# ik_breakout__atxmega32E5.net
KiCad netlist of a schematic drawn in EAGLE
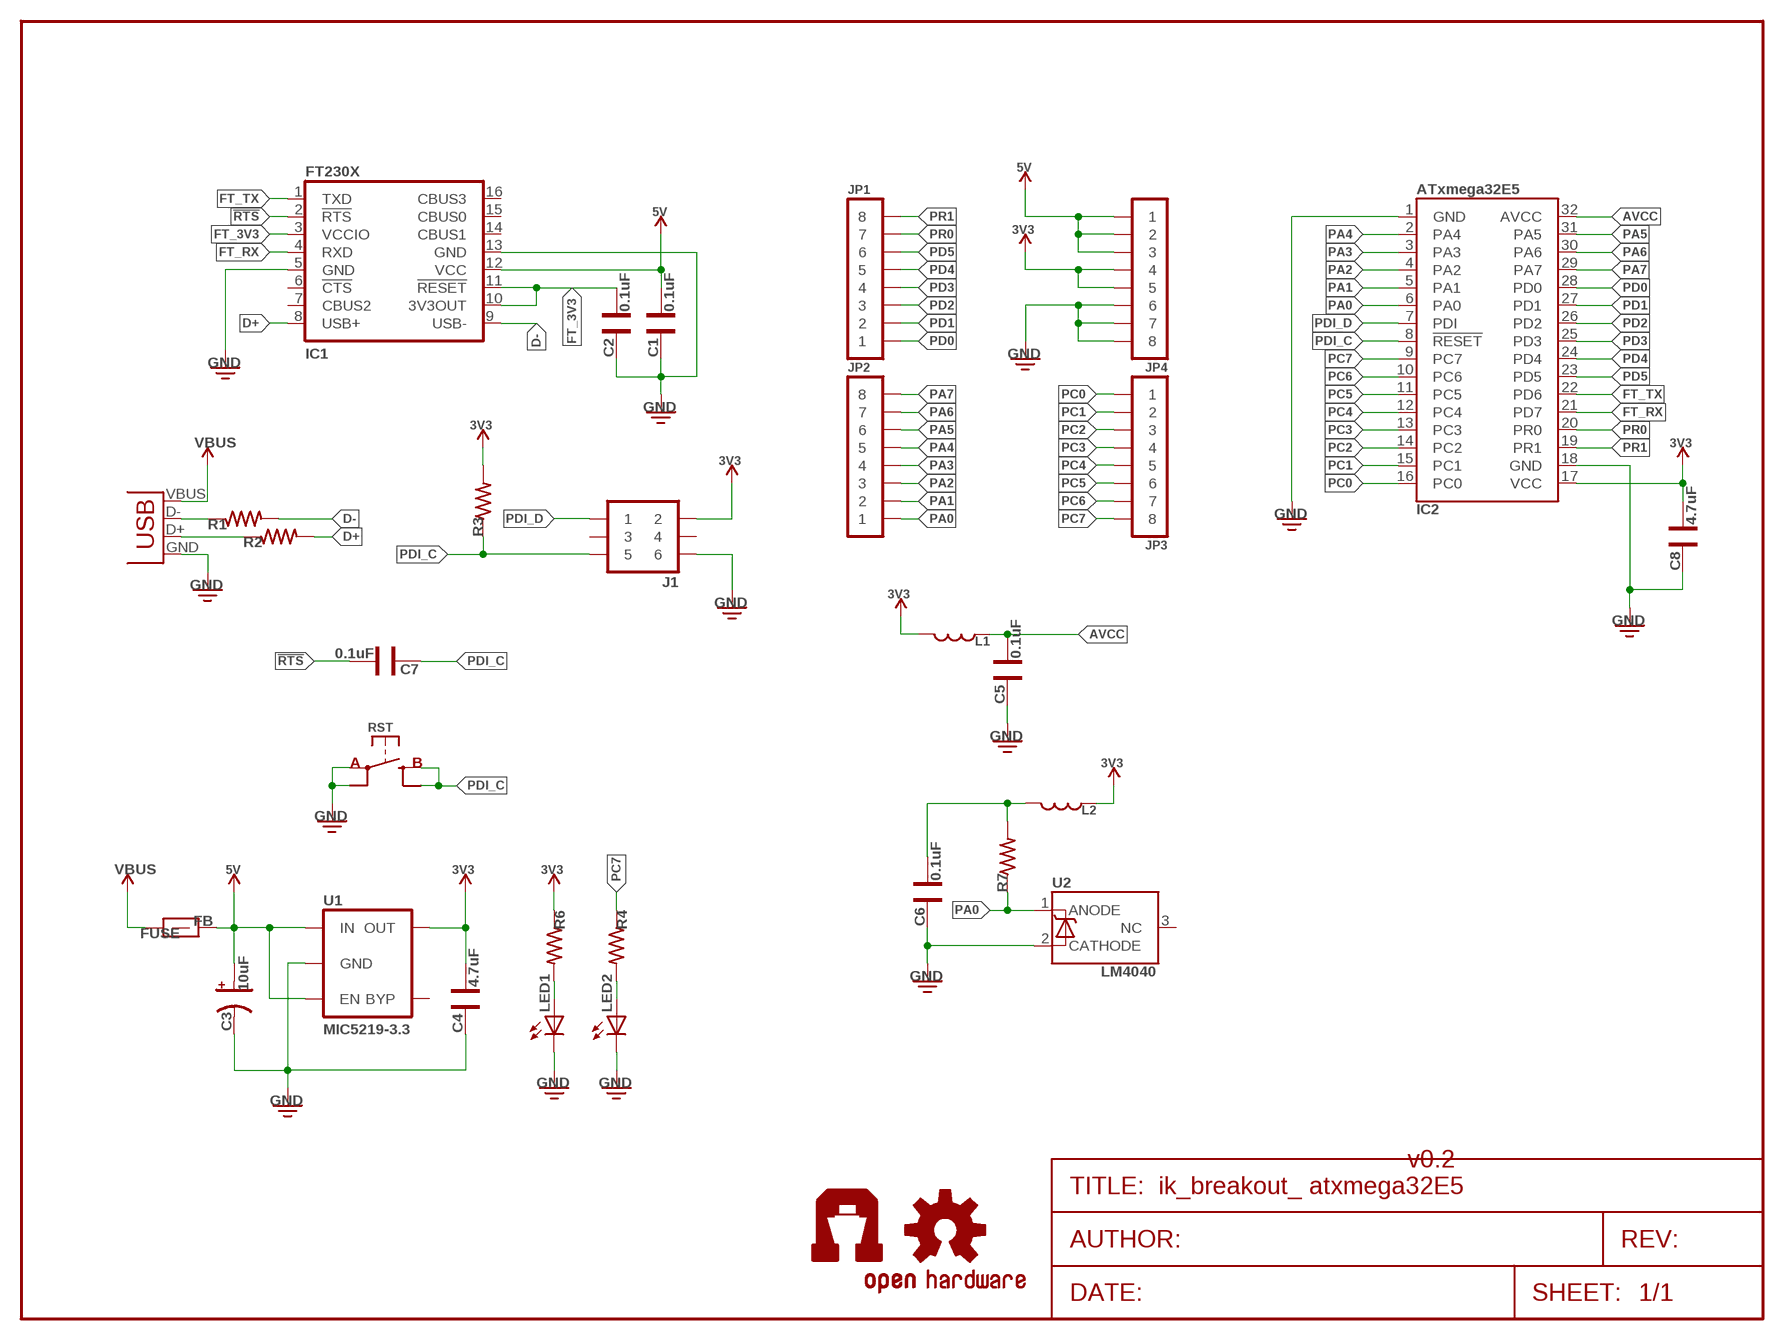
[diagram p0: schematic, sheet 1]

(export (version "E")
  (design (tool "Eeschema 10.0.6"))
  (components
    (comp (ref "C1")
      (value "0.1uF")
      (footprint "eagle-import:CAP-0603")
      (libsource (lib "eagle-import") (part "CAP0603"))
    )
    (comp (ref "C2")
      (value "0.1uF")
      (footprint "eagle-import:CAP-0603")
      (libsource (lib "eagle-import") (part "CAP0603"))
    )
    (comp (ref "C3")
      (value "10uF")
      (footprint "eagle-import:CAP-POL-EIA3216")
      (libsource (lib "eagle-import") (part "CAP-POLEIA3216"))
    )
    (comp (ref "C4")
      (value "4.7uF")
      (footprint "eagle-import:CAP-0603")
      (libsource (lib "eagle-import") (part "CAP0603"))
    )
    (comp (ref "C5")
      (value "0.1uF")
      (footprint "eagle-import:CAP-0603")
      (libsource (lib "eagle-import") (part "CAP0603"))
    )
    (comp (ref "C6")
      (value "0.1uF")
      (footprint "eagle-import:CAP-0603")
      (libsource (lib "eagle-import") (part "CAP0603"))
    )
    (comp (ref "C7")
      (value "0.1uF")
      (footprint "eagle-import:CAP-0603")
      (libsource (lib "eagle-import") (part "CAP0603"))
    )
    (comp (ref "C8")
      (value "4.7uF")
      (footprint "eagle-import:CAP-0603")
      (libsource (lib "eagle-import") (part "CAP0603"))
    )
    (comp (ref "FUSE")
      (value "FB")
      (footprint "eagle-import:FB-0603")
      (libsource (lib "eagle-import") (part "FB"))
    )
    (comp (ref "IC1")
      (value "FT230X")
      (footprint "eagle-import:SSOP-16-FTDI")
      (libsource (lib "eagle-import") (part "FT230X"))
    )
    (comp (ref "IC2")
      (value "ATXMEGA32E5")
      (footprint "eagle-import:TQFP32-08")
      (libsource (lib "eagle-import") (part "ATXMEGA32E5"))
    )
    (comp (ref "J1")
      (value "2X03")
      (footprint "eagle-import:2X03")
      (libsource (lib "eagle-import") (part "2X03"))
    )
    (comp (ref "JP1")
      (value "1X08NOFIRST")
      (footprint "eagle-import:1X08-NOFIRST")
      (libsource (lib "eagle-import") (part "1X08NOFIRST"))
    )
    (comp (ref "JP2")
      (value "1X08NOFIRST")
      (footprint "eagle-import:1X08-NOFIRST")
      (libsource (lib "eagle-import") (part "1X08NOFIRST"))
    )
    (comp (ref "JP3")
      (value "1X08NOFIRST")
      (footprint "eagle-import:1X08-NOFIRST")
      (libsource (lib "eagle-import") (part "1X08NOFIRST"))
    )
    (comp (ref "JP4")
      (value "1X08NOFIRST")
      (footprint "eagle-import:1X08-NOFIRST")
      (libsource (lib "eagle-import") (part "1X08NOFIRST"))
    )
    (comp (ref "L1")
      (value "IND0603")
      (footprint "eagle-import:IND-0603")
      (libsource (lib "eagle-import") (part "IND0603"))
    )
    (comp (ref "L2")
      (value "IND0603")
      (footprint "eagle-import:IND-0603")
      (libsource (lib "eagle-import") (part "IND0603"))
    )
    (comp (ref "LED1")
      (value "LED0603")
      (footprint "eagle-import:LED-0603")
      (libsource (lib "eagle-import") (part "LED0603"))
    )
    (comp (ref "LED2")
      (value "LED0603")
      (footprint "eagle-import:LED-0603")
      (libsource (lib "eagle-import") (part "LED0603"))
    )
    (comp (ref "LOGO1")
      (value "OSHW-LOGOS")
      (footprint "eagle-import:OSHW-LOGO-S")
      (libsource (lib "eagle-import") (part "OSHW-LOGOS"))
    )
    (comp (ref "R1")
      (value "RES0603")
      (footprint "eagle-import:RES-0603")
      (libsource (lib "eagle-import") (part "RES0603"))
    )
    (comp (ref "R2")
      (value "RES0603")
      (footprint "eagle-import:RES-0603")
      (libsource (lib "eagle-import") (part "RES0603"))
    )
    (comp (ref "R3")
      (value "RES0603")
      (footprint "eagle-import:RES-0603")
      (libsource (lib "eagle-import") (part "RES0603"))
    )
    (comp (ref "R4")
      (value "RES0603")
      (footprint "eagle-import:RES-0603")
      (libsource (lib "eagle-import") (part "RES0603"))
    )
    (comp (ref "R6")
      (value "RES0603")
      (footprint "eagle-import:RES-0603")
      (libsource (lib "eagle-import") (part "RES0603"))
    )
    (comp (ref "R7")
      (value "RES0603")
      (footprint "eagle-import:RES-0603")
      (libsource (lib "eagle-import") (part "RES0603"))
    )
    (comp (ref "RST")
      (value "SW-SPSTSMD03X026")
      (footprint "eagle-import:SW-SPST-SMD03X026")
      (libsource (lib "eagle-import") (part "SW-SPSTSMD03X026"))
    )
    (comp (ref "U$3")
      (value "AI-LOGOXS")
      (footprint "eagle-import:AI-LOGO-XS")
      (libsource (lib "eagle-import") (part "AI-LOGOXS"))
    )
    (comp (ref "U1")
      (value "MIC5219-3.3")
      (footprint "eagle-import:SOT23-5")
      (libsource (lib "eagle-import") (part "MIC5219-3.3"))
    )
    (comp (ref "U2")
      (value "LM4040")
      (footprint "eagle-import:SOT23-3")
      (libsource (lib "eagle-import") (part "LM4040"))
    )
    (comp (ref "USB1")
      (value "USBMICROB-TH")
      (footprint "eagle-import:USB-MICROB-TH")
      (libsource (lib "eagle-import") (part "USBMICROB-TH"))
    )
  )
  (nets
    (net (code "1") (name "/~{RTS}") (class "Default")
      (node (ref "C7") (pin "1") (pinfunction "1_1") (pintype "passive"))
      (node (ref "IC1") (pin "2") (pinfunction "~{RTS}_2") (pintype "bidirectional"))
    )
    (net (code "2") (name "3V3") (class "Default")
      (node (ref "C4") (pin "1") (pinfunction "1_1") (pintype "passive"))
      (node (ref "C8") (pin "1") (pinfunction "1_1") (pintype "passive"))
      (node (ref "IC2") (pin "17") (pinfunction "VCC_17") (pintype "bidirectional"))
      (node (ref "J1") (pin "2") (pinfunction "2_2") (pintype "bidirectional"))
      (node (ref "JP4") (pin "4") (pinfunction "4_4") (pintype "bidirectional"))
      (node (ref "JP4") (pin "5") (pinfunction "5_5") (pintype "bidirectional"))
      (node (ref "L1") (pin "1") (pinfunction "1_1") (pintype "passive"))
      (node (ref "L2") (pin "2") (pinfunction "2_2") (pintype "passive"))
      (node (ref "R3") (pin "2") (pinfunction "2_2") (pintype "passive"))
      (node (ref "R6") (pin "1") (pinfunction "1_1") (pintype "passive"))
      (node (ref "U1") (pin "5") (pinfunction "OUT_5") (pintype "passive"))
    )
    (net (code "3") (name "5V") (class "Default")
      (node (ref "C1") (pin "1") (pinfunction "1_1") (pintype "passive"))
      (node (ref "C3") (pin "A") (pinfunction "A_A") (pintype "passive"))
      (node (ref "FUSE") (pin "2") (pinfunction "P$2_2") (pintype "bidirectional"))
      (node (ref "IC1") (pin "12") (pinfunction "VCC_12") (pintype "power_in"))
      (node (ref "JP4") (pin "1") (pinfunction "1_1") (pintype "bidirectional"))
      (node (ref "JP4") (pin "2") (pinfunction "2_2") (pintype "bidirectional"))
      (node (ref "JP4") (pin "3") (pinfunction "3_3") (pintype "bidirectional"))
      (node (ref "U1") (pin "1") (pinfunction "IN_1") (pintype "input"))
      (node (ref "U1") (pin "3") (pinfunction "EN_3") (pintype "input"))
    )
    (net (code "4") (name "AVCC") (class "Default")
      (node (ref "C5") (pin "1") (pinfunction "1_1") (pintype "passive"))
      (node (ref "IC2") (pin "32") (pinfunction "AVCC_32") (pintype "bidirectional"))
      (node (ref "L1") (pin "2") (pinfunction "2_2") (pintype "passive"))
    )
    (net (code "5") (name "D+") (class "Default")
      (node (ref "IC1") (pin "8") (pinfunction "USB+_8") (pintype "output"))
      (node (ref "R2") (pin "2") (pinfunction "2_2") (pintype "passive"))
    )
    (net (code "6") (name "D-") (class "Default")
      (node (ref "IC1") (pin "9") (pinfunction "USB-_9") (pintype "input"))
      (node (ref "R1") (pin "2") (pinfunction "2_2") (pintype "passive"))
    )
    (net (code "7") (name "FT_3V3") (class "Default")
      (node (ref "C2") (pin "1") (pinfunction "1_1") (pintype "passive"))
      (node (ref "IC1") (pin "10") (pinfunction "3V3OUT_10") (pintype "power_in"))
      (node (ref "IC1") (pin "11") (pinfunction "~{RESET}_11") (pintype "bidirectional"))
      (node (ref "IC1") (pin "3") (pinfunction "VCCIO_3") (pintype "power_in"))
    )
    (net (code "8") (name "FT_RX") (class "Default")
      (node (ref "IC1") (pin "4") (pinfunction "RXD_4") (pintype "input"))
      (node (ref "IC2") (pin "21") (pinfunction "PD7_21") (pintype "bidirectional"))
    )
    (net (code "9") (name "FT_TX") (class "Default")
      (node (ref "IC1") (pin "1") (pinfunction "TXD_1") (pintype "output"))
      (node (ref "IC2") (pin "22") (pinfunction "PD6_22") (pintype "bidirectional"))
    )
    (net (code "10") (name "GND") (class "Default")
      (node (ref "C1") (pin "2") (pinfunction "2_2") (pintype "passive"))
      (node (ref "C2") (pin "2") (pinfunction "2_2") (pintype "passive"))
      (node (ref "C3") (pin "C") (pinfunction "C_C") (pintype "passive"))
      (node (ref "C4") (pin "2") (pinfunction "2_2") (pintype "passive"))
      (node (ref "C5") (pin "2") (pinfunction "2_2") (pintype "passive"))
      (node (ref "C6") (pin "2") (pinfunction "2_2") (pintype "passive"))
      (node (ref "C8") (pin "2") (pinfunction "2_2") (pintype "passive"))
      (node (ref "IC1") (pin "13") (pinfunction "GND_13") (pintype "power_in"))
      (node (ref "IC1") (pin "5") (pinfunction "GND_5") (pintype "power_in"))
      (node (ref "IC2") (pin "1") (pinfunction "GND_1") (pintype "bidirectional"))
      (node (ref "IC2") (pin "18") (pinfunction "GND_18") (pintype "bidirectional"))
      (node (ref "J1") (pin "6") (pinfunction "6_6") (pintype "bidirectional"))
      (node (ref "JP4") (pin "6") (pinfunction "6_6") (pintype "bidirectional"))
      (node (ref "JP4") (pin "7") (pinfunction "7_7") (pintype "bidirectional"))
      (node (ref "JP4") (pin "8") (pinfunction "8_8") (pintype "bidirectional"))
      (node (ref "LED1") (pin "C") (pinfunction "C_C") (pintype "passive"))
      (node (ref "LED2") (pin "C") (pinfunction "C_C") (pintype "passive"))
      (node (ref "RST") (pin "1") (pinfunction "A_1") (pintype "passive"))
      (node (ref "RST") (pin "2") (pinfunction "A_2") (pintype "passive"))
      (node (ref "U1") (pin "2") (pinfunction "GND_2") (pintype "input"))
      (node (ref "U2") (pin "2") (pinfunction "CATHODE_2") (pintype "bidirectional"))
      (node (ref "USB1") (pin "GND") (pinfunction "GND_GND") (pintype "bidirectional"))
    )
    (net (code "11") (name "Net-(C6-Pad1)") (class "Default")
      (node (ref "C6") (pin "1") (pinfunction "1_1") (pintype "passive"))
      (node (ref "L2") (pin "1") (pinfunction "1_1") (pintype "passive"))
      (node (ref "R7") (pin "2") (pinfunction "2_2") (pintype "passive"))
    )
    (net (code "12") (name "Net-(LED1-PadA)") (class "Default")
      (node (ref "LED1") (pin "A") (pinfunction "A_A") (pintype "passive"))
      (node (ref "R6") (pin "2") (pinfunction "2_2") (pintype "passive"))
    )
    (net (code "13") (name "Net-(LED2-PadA)") (class "Default")
      (node (ref "LED2") (pin "A") (pinfunction "A_A") (pintype "passive"))
      (node (ref "R4") (pin "2") (pinfunction "2_2") (pintype "passive"))
    )
    (net (code "14") (name "Net-(R1-Pad1)") (class "Default")
      (node (ref "R1") (pin "1") (pinfunction "1_1") (pintype "passive"))
      (node (ref "USB1") (pin "D-") (pinfunction "D-_D-") (pintype "bidirectional"))
    )
    (net (code "15") (name "Net-(R2-Pad1)") (class "Default")
      (node (ref "R2") (pin "1") (pinfunction "1_1") (pintype "passive"))
      (node (ref "USB1") (pin "D+") (pinfunction "D+_D+") (pintype "bidirectional"))
    )
    (net (code "16") (name "PA0") (class "Default")
      (node (ref "IC2") (pin "6") (pinfunction "PA0_6") (pintype "bidirectional"))
      (node (ref "JP2") (pin "1") (pinfunction "1_1") (pintype "bidirectional"))
      (node (ref "R7") (pin "1") (pinfunction "1_1") (pintype "passive"))
      (node (ref "U2") (pin "1") (pinfunction "ANODE_1") (pintype "bidirectional"))
    )
    (net (code "17") (name "PA1") (class "Default")
      (node (ref "IC2") (pin "5") (pinfunction "PA1_5") (pintype "bidirectional"))
      (node (ref "JP2") (pin "2") (pinfunction "2_2") (pintype "bidirectional"))
    )
    (net (code "18") (name "PA2") (class "Default")
      (node (ref "IC2") (pin "4") (pinfunction "PA2_4") (pintype "bidirectional"))
      (node (ref "JP2") (pin "3") (pinfunction "3_3") (pintype "bidirectional"))
    )
    (net (code "19") (name "PA3") (class "Default")
      (node (ref "IC2") (pin "3") (pinfunction "PA3_3") (pintype "bidirectional"))
      (node (ref "JP2") (pin "4") (pinfunction "4_4") (pintype "bidirectional"))
    )
    (net (code "20") (name "PA4") (class "Default")
      (node (ref "IC2") (pin "2") (pinfunction "PA4_2") (pintype "bidirectional"))
      (node (ref "JP2") (pin "5") (pinfunction "5_5") (pintype "bidirectional"))
    )
    (net (code "21") (name "PA5") (class "Default")
      (node (ref "IC2") (pin "31") (pinfunction "PA5_31") (pintype "bidirectional"))
      (node (ref "JP2") (pin "6") (pinfunction "6_6") (pintype "bidirectional"))
    )
    (net (code "22") (name "PA6") (class "Default")
      (node (ref "IC2") (pin "30") (pinfunction "PA6_30") (pintype "bidirectional"))
      (node (ref "JP2") (pin "7") (pinfunction "7_7") (pintype "bidirectional"))
    )
    (net (code "23") (name "PA7") (class "Default")
      (node (ref "IC2") (pin "29") (pinfunction "PA7_29") (pintype "bidirectional"))
      (node (ref "JP2") (pin "8") (pinfunction "8_8") (pintype "bidirectional"))
    )
    (net (code "24") (name "PC0") (class "Default")
      (node (ref "IC2") (pin "16") (pinfunction "PC0_16") (pintype "bidirectional"))
      (node (ref "JP3") (pin "1") (pinfunction "1_1") (pintype "bidirectional"))
    )
    (net (code "25") (name "PC1") (class "Default")
      (node (ref "IC2") (pin "15") (pinfunction "PC1_15") (pintype "bidirectional"))
      (node (ref "JP3") (pin "2") (pinfunction "2_2") (pintype "bidirectional"))
    )
    (net (code "26") (name "PC2") (class "Default")
      (node (ref "IC2") (pin "14") (pinfunction "PC2_14") (pintype "bidirectional"))
      (node (ref "JP3") (pin "3") (pinfunction "3_3") (pintype "bidirectional"))
    )
    (net (code "27") (name "PC3") (class "Default")
      (node (ref "IC2") (pin "13") (pinfunction "PC3_13") (pintype "bidirectional"))
      (node (ref "JP3") (pin "4") (pinfunction "4_4") (pintype "bidirectional"))
    )
    (net (code "28") (name "PC4") (class "Default")
      (node (ref "IC2") (pin "12") (pinfunction "PC4_12") (pintype "bidirectional"))
      (node (ref "JP3") (pin "5") (pinfunction "5_5") (pintype "bidirectional"))
    )
    (net (code "29") (name "PC5") (class "Default")
      (node (ref "IC2") (pin "11") (pinfunction "PC5_11") (pintype "bidirectional"))
      (node (ref "JP3") (pin "6") (pinfunction "6_6") (pintype "bidirectional"))
    )
    (net (code "30") (name "PC6") (class "Default")
      (node (ref "IC2") (pin "10") (pinfunction "PC6_10") (pintype "bidirectional"))
      (node (ref "JP3") (pin "7") (pinfunction "7_7") (pintype "bidirectional"))
    )
    (net (code "31") (name "PC7") (class "Default")
      (node (ref "IC2") (pin "9") (pinfunction "PC7_9") (pintype "bidirectional"))
      (node (ref "JP3") (pin "8") (pinfunction "8_8") (pintype "bidirectional"))
      (node (ref "R4") (pin "1") (pinfunction "1_1") (pintype "passive"))
    )
    (net (code "32") (name "PD0") (class "Default")
      (node (ref "IC2") (pin "28") (pinfunction "PD0_28") (pintype "bidirectional"))
      (node (ref "JP1") (pin "1") (pinfunction "1_1") (pintype "bidirectional"))
    )
    (net (code "33") (name "PD1") (class "Default")
      (node (ref "IC2") (pin "27") (pinfunction "PD1_27") (pintype "bidirectional"))
      (node (ref "JP1") (pin "2") (pinfunction "2_2") (pintype "bidirectional"))
    )
    (net (code "34") (name "PD2") (class "Default")
      (node (ref "IC2") (pin "26") (pinfunction "PD2_26") (pintype "bidirectional"))
      (node (ref "JP1") (pin "3") (pinfunction "3_3") (pintype "bidirectional"))
    )
    (net (code "35") (name "PD3") (class "Default")
      (node (ref "IC2") (pin "25") (pinfunction "PD3_25") (pintype "bidirectional"))
      (node (ref "JP1") (pin "4") (pinfunction "4_4") (pintype "bidirectional"))
    )
    (net (code "36") (name "PD4") (class "Default")
      (node (ref "IC2") (pin "24") (pinfunction "PD4_24") (pintype "bidirectional"))
      (node (ref "JP1") (pin "5") (pinfunction "5_5") (pintype "bidirectional"))
    )
    (net (code "37") (name "PD5") (class "Default")
      (node (ref "IC2") (pin "23") (pinfunction "PD5_23") (pintype "bidirectional"))
      (node (ref "JP1") (pin "6") (pinfunction "6_6") (pintype "bidirectional"))
    )
    (net (code "38") (name "PDI_C") (class "Default")
      (node (ref "C7") (pin "2") (pinfunction "2_2") (pintype "passive"))
      (node (ref "IC2") (pin "8") (pinfunction "~{RESET}_8") (pintype "bidirectional"))
      (node (ref "J1") (pin "5") (pinfunction "5_5") (pintype "bidirectional"))
      (node (ref "R3") (pin "1") (pinfunction "1_1") (pintype "passive"))
      (node (ref "RST") (pin "3") (pinfunction "B_3") (pintype "passive"))
      (node (ref "RST") (pin "4") (pinfunction "B_4") (pintype "passive"))
    )
    (net (code "39") (name "PDI_D") (class "Default")
      (node (ref "IC2") (pin "7") (pinfunction "PDI_7") (pintype "bidirectional"))
      (node (ref "J1") (pin "1") (pinfunction "1_1") (pintype "bidirectional"))
    )
    (net (code "40") (name "PR0") (class "Default")
      (node (ref "IC2") (pin "20") (pinfunction "PR0_20") (pintype "bidirectional"))
      (node (ref "JP1") (pin "7") (pinfunction "7_7") (pintype "bidirectional"))
    )
    (net (code "41") (name "PR1") (class "Default")
      (node (ref "IC2") (pin "19") (pinfunction "PR1_19") (pintype "bidirectional"))
      (node (ref "JP1") (pin "8") (pinfunction "8_8") (pintype "bidirectional"))
    )
    (net (code "42") (name "VBUS") (class "Default")
      (node (ref "FUSE") (pin "1") (pinfunction "P$1_1") (pintype "passive"))
      (node (ref "USB1") (pin "VBUS") (pinfunction "VBUS_VBUS") (pintype "bidirectional"))
    )
    (net (code "43") (name "unconnected-(IC1-CBUS0-Pad15)") (class "Default")
      (node (ref "IC1") (pin "15") (pinfunction "CBUS0_15") (pintype "bidirectional"))
    )
    (net (code "44") (name "unconnected-(IC1-CBUS1-Pad14)") (class "Default")
      (node (ref "IC1") (pin "14") (pinfunction "CBUS1_14") (pintype "bidirectional"))
    )
    (net (code "45") (name "unconnected-(IC1-CBUS2-Pad7)") (class "Default")
      (node (ref "IC1") (pin "7") (pinfunction "CBUS2_7") (pintype "bidirectional"))
    )
    (net (code "46") (name "unconnected-(IC1-CBUS3-Pad16)") (class "Default")
      (node (ref "IC1") (pin "16") (pinfunction "CBUS3_16") (pintype "bidirectional"))
    )
    (net (code "47") (name "unconnected-(IC1-~{CTS}-Pad6)") (class "Default")
      (node (ref "IC1") (pin "6") (pinfunction "~{CTS}_6") (pintype "bidirectional"))
    )
    (net (code "48") (name "unconnected-(J1-Pad3)") (class "Default")
      (node (ref "J1") (pin "3") (pinfunction "3_3") (pintype "bidirectional"))
    )
    (net (code "49") (name "unconnected-(J1-Pad4)") (class "Default")
      (node (ref "J1") (pin "4") (pinfunction "4_4") (pintype "bidirectional"))
    )
    (net (code "50") (name "unconnected-(U1-BYP-Pad4)") (class "Default")
      (node (ref "U1") (pin "4") (pinfunction "BYP_4") (pintype "input"))
    )
    (net (code "51") (name "unconnected-(U2-NC-Pad3)") (class "Default")
      (node (ref "U2") (pin "3") (pinfunction "NC_3") (pintype "bidirectional"))
    )
  )
)
